# novanet.net
KiCad netlist of a schematic drawn in EAGLE
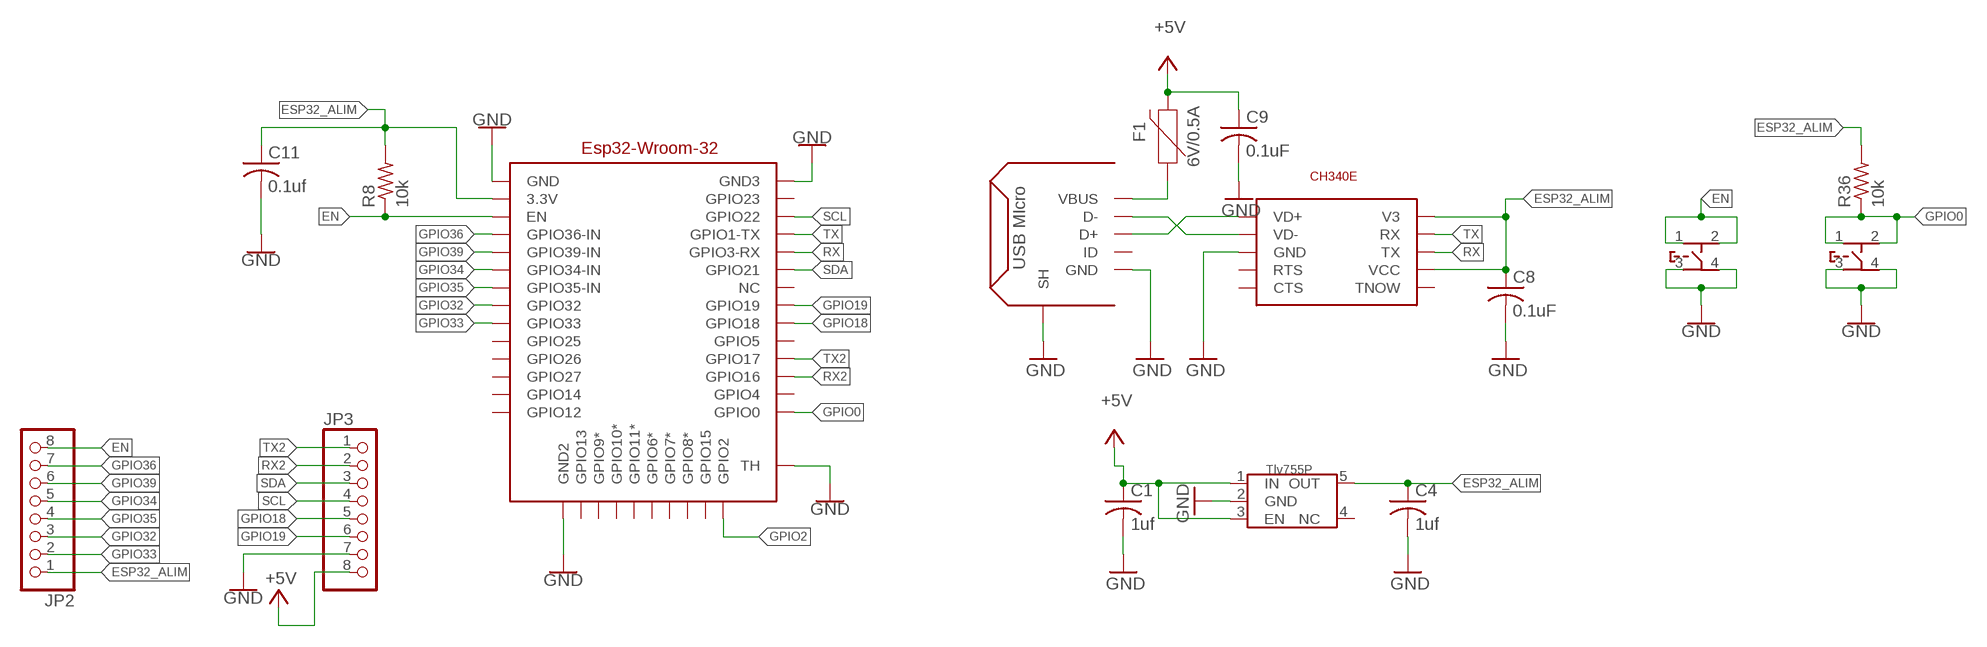
[diagram p0: schematic, sheet 1]

(export (version "E")
  (design (tool "Eeschema 10.0.6"))
  (components
    (comp (ref "C1")
      (value "1uf")
      (footprint "eagle-import:C0603")
      (libsource (lib "eagle-import") (part "C-USC0603"))
    )
    (comp (ref "C4")
      (value "1uf")
      (footprint "eagle-import:C0603")
      (libsource (lib "eagle-import") (part "C-USC0603"))
    )
    (comp (ref "C8")
      (value "0.1uF")
      (footprint "eagle-import:C0603")
      (libsource (lib "eagle-import") (part "C-USC0603"))
    )
    (comp (ref "C9")
      (value "0.1uF")
      (footprint "eagle-import:C0603")
      (libsource (lib "eagle-import") (part "C-USC0603"))
    )
    (comp (ref "C11")
      (value "0.1uf")
      (footprint "eagle-import:C0603")
      (libsource (lib "eagle-import") (part "C-USC0603"))
    )
    (comp (ref "F1")
      (value "6V/0.5A")
      (footprint "eagle-import:1206")
      (libsource (lib "eagle-import") (part "PPTC_HALF-AMP"))
    )
    (comp (ref "JP2")
      (value "PINHD-1X8")
      (footprint "eagle-import:1X08")
      (libsource (lib "eagle-import") (part "PINHD-1X8"))
    )
    (comp (ref "JP3")
      (value "PINHD-1X8")
      (footprint "eagle-import:1X08")
      (libsource (lib "eagle-import") (part "PINHD-1X8"))
    )
    (comp (ref "R8")
      (value "10k")
      (footprint "eagle-import:R0603")
      (libsource (lib "eagle-import") (part "R-US_R0603"))
    )
    (comp (ref "R36")
      (value "10k")
      (footprint "eagle-import:R0603")
      (libsource (lib "eagle-import") (part "R-US_R0603"))
    )
    (comp (ref "U$1")
      (value "TLV755P-3.3SOT-23-5")
      (footprint "eagle-import:DBV_R-PDSO-G5")
      (libsource (lib "eagle-import") (part "TLV755P-3.3SOT-23-5"))
    )
    (comp (ref "U$3")
      (value "CH340E")
      (footprint "eagle-import:MSOP-10")
      (libsource (lib "eagle-import") (part "CH340E"))
    )
    (comp (ref "U$4")
      (value "ESP32-WROM-32")
      (footprint "eagle-import:ESP-32FOOTPRINT")
      (libsource (lib "eagle-import") (part "ESP32-WROM-32"))
    )
    (comp (ref "U$14")
      (value "USB-MICROTIPOC")
      (footprint "eagle-import:USB-MICRO")
      (libsource (lib "eagle-import") (part "USB-MICROTIPOC"))
    )
    (comp (ref "U$22")
      (value "XUNPU")
      (footprint "eagle-import:TS-1089S")
      (libsource (lib "eagle-import") (part "XUNPU"))
    )
    (comp (ref "U$23")
      (value "XUNPU")
      (footprint "eagle-import:TS-1089S")
      (libsource (lib "eagle-import") (part "XUNPU"))
    )
  )
  (nets
    (net (code "1") (name "+5V") (class "Default")
      (node (ref "C1") (pin "1") (pinfunction "1_1") (pintype "passive"))
      (node (ref "C9") (pin "1") (pinfunction "1_1") (pintype "passive"))
      (node (ref "F1") (pin "2") (pinfunction "2_2") (pintype "bidirectional"))
      (node (ref "JP3") (pin "8") (pinfunction "8_8") (pintype "passive"))
      (node (ref "U$1") (pin "1") (pinfunction "IN_1") (pintype "bidirectional"))
      (node (ref "U$1") (pin "3") (pinfunction "EN_3") (pintype "bidirectional"))
    )
    (net (code "2") (name "EN") (class "Default")
      (node (ref "JP2") (pin "8") (pinfunction "8_8") (pintype "passive"))
      (node (ref "R8") (pin "1") (pinfunction "1_1") (pintype "passive"))
      (node (ref "U$22") (pin "1") (pinfunction "1_1") (pintype "bidirectional"))
      (node (ref "U$22") (pin "2") (pinfunction "2_2") (pintype "bidirectional"))
      (node (ref "U$4") (pin "EN") (pinfunction "EN_EN") (pintype "bidirectional"))
    )
    (net (code "3") (name "ESP32_ALIM") (class "Default")
      (node (ref "C11") (pin "1") (pinfunction "1_1") (pintype "passive"))
      (node (ref "C4") (pin "1") (pinfunction "1_1") (pintype "passive"))
      (node (ref "C8") (pin "1") (pinfunction "1_1") (pintype "passive"))
      (node (ref "JP2") (pin "1") (pinfunction "1_1") (pintype "passive"))
      (node (ref "R36") (pin "2") (pinfunction "2_2") (pintype "passive"))
      (node (ref "R8") (pin "2") (pinfunction "2_2") (pintype "passive"))
      (node (ref "U$1") (pin "5") (pinfunction "OUT_5") (pintype "bidirectional"))
      (node (ref "U$3") (pin "V3") (pinfunction "V3_V3") (pintype "bidirectional"))
      (node (ref "U$3") (pin "VCC") (pinfunction "VCC_VCC") (pintype "bidirectional"))
      (node (ref "U$4") (pin "3.3V") (pinfunction "3.3V_3.3V") (pintype "bidirectional"))
    )
    (net (code "4") (name "GND") (class "Default")
      (node (ref "C1") (pin "2") (pinfunction "2_2") (pintype "passive"))
      (node (ref "C11") (pin "2") (pinfunction "2_2") (pintype "passive"))
      (node (ref "C4") (pin "2") (pinfunction "2_2") (pintype "passive"))
      (node (ref "C8") (pin "2") (pinfunction "2_2") (pintype "passive"))
      (node (ref "C9") (pin "2") (pinfunction "2_2") (pintype "passive"))
      (node (ref "JP3") (pin "7") (pinfunction "7_7") (pintype "passive"))
      (node (ref "U$1") (pin "2") (pinfunction "GND_2") (pintype "bidirectional"))
      (node (ref "U$14") (pin "GND") (pinfunction "GND_GND") (pintype "bidirectional"))
      (node (ref "U$14") (pin "P$1") (pinfunction "SH_P$1") (pintype "bidirectional"))
      (node (ref "U$14") (pin "P$2") (pinfunction "SH_P$2") (pintype "bidirectional"))
      (node (ref "U$14") (pin "P$3") (pinfunction "SH_P$3") (pintype "bidirectional"))
      (node (ref "U$14") (pin "P$4") (pinfunction "SH_P$4") (pintype "bidirectional"))
      (node (ref "U$22") (pin "3") (pinfunction "3_3") (pintype "bidirectional"))
      (node (ref "U$22") (pin "4") (pinfunction "4_4") (pintype "bidirectional"))
      (node (ref "U$23") (pin "3") (pinfunction "3_3") (pintype "bidirectional"))
      (node (ref "U$23") (pin "4") (pinfunction "4_4") (pintype "bidirectional"))
      (node (ref "U$3") (pin "GND") (pinfunction "GND_GND") (pintype "bidirectional"))
      (node (ref "U$4") (pin "GND") (pinfunction "GND_GND") (pintype "bidirectional"))
      (node (ref "U$4") (pin "GND2") (pinfunction "GND2_GND2") (pintype "bidirectional"))
      (node (ref "U$4") (pin "GND3") (pinfunction "GND3_GND3") (pintype "bidirectional"))
      (node (ref "U$4") (pin "TH") (pinfunction "TH_TH") (pintype "bidirectional"))
    )
    (net (code "5") (name "GPIO0") (class "Default")
      (node (ref "R36") (pin "1") (pinfunction "1_1") (pintype "passive"))
      (node (ref "U$23") (pin "1") (pinfunction "1_1") (pintype "bidirectional"))
      (node (ref "U$23") (pin "2") (pinfunction "2_2") (pintype "bidirectional"))
      (node (ref "U$4") (pin "GPIO0") (pinfunction "GPIO0_GPIO0") (pintype "bidirectional"))
    )
    (net (code "6") (name "GPIO2") (class "Default")
      (node (ref "U$4") (pin "GPIO2") (pinfunction "GPIO2_GPIO2") (pintype "bidirectional"))
    )
    (net (code "7") (name "GPIO18") (class "Default")
      (node (ref "JP3") (pin "5") (pinfunction "5_5") (pintype "passive"))
      (node (ref "U$4") (pin "GPIO18") (pinfunction "GPIO18_GPIO18") (pintype "bidirectional"))
    )
    (net (code "8") (name "GPIO19") (class "Default")
      (node (ref "JP3") (pin "6") (pinfunction "6_6") (pintype "passive"))
      (node (ref "U$4") (pin "GPIO19") (pinfunction "GPIO19_GPIO19") (pintype "bidirectional"))
    )
    (net (code "9") (name "GPIO32") (class "Default")
      (node (ref "JP2") (pin "3") (pinfunction "3_3") (pintype "passive"))
      (node (ref "U$4") (pin "GPIO32") (pinfunction "GPIO32_GPIO32") (pintype "bidirectional"))
    )
    (net (code "10") (name "GPIO33") (class "Default")
      (node (ref "JP2") (pin "2") (pinfunction "2_2") (pintype "passive"))
      (node (ref "U$4") (pin "GPIO33") (pinfunction "GPIO33_GPIO33") (pintype "bidirectional"))
    )
    (net (code "11") (name "GPIO34") (class "Default")
      (node (ref "JP2") (pin "5") (pinfunction "5_5") (pintype "passive"))
      (node (ref "U$4") (pin "GPIO34") (pinfunction "GPIO34-IN_GPIO34") (pintype "bidirectional"))
    )
    (net (code "12") (name "GPIO35") (class "Default")
      (node (ref "JP2") (pin "4") (pinfunction "4_4") (pintype "passive"))
      (node (ref "U$4") (pin "GPIO35") (pinfunction "GPIO35-IN_GPIO35") (pintype "bidirectional"))
    )
    (net (code "13") (name "GPIO36") (class "Default")
      (node (ref "JP2") (pin "7") (pinfunction "7_7") (pintype "passive"))
      (node (ref "U$4") (pin "GPIO36") (pinfunction "GPIO36-IN_GPIO36") (pintype "bidirectional"))
    )
    (net (code "14") (name "GPIO39") (class "Default")
      (node (ref "JP2") (pin "6") (pinfunction "6_6") (pintype "passive"))
      (node (ref "U$4") (pin "GPIO39") (pinfunction "GPIO39-IN_GPIO39") (pintype "bidirectional"))
    )
    (net (code "15") (name "Net-(F1-Pad1)") (class "Default")
      (node (ref "F1") (pin "1") (pinfunction "1_1") (pintype "bidirectional"))
      (node (ref "U$14") (pin "VBUS") (pinfunction "VBUS_VBUS") (pintype "bidirectional"))
    )
    (net (code "16") (name "Net-(U$14-PadD+)") (class "Default")
      (node (ref "U$14") (pin "D+") (pinfunction "D+_D+") (pintype "bidirectional"))
      (node (ref "U$3") (pin "VD+") (pinfunction "VD+_VD+") (pintype "bidirectional"))
    )
    (net (code "17") (name "Net-(U$14-PadD-)") (class "Default")
      (node (ref "U$14") (pin "D-") (pinfunction "D-_D-") (pintype "bidirectional"))
      (node (ref "U$3") (pin "VD-") (pinfunction "VD-_VD-") (pintype "bidirectional"))
    )
    (net (code "18") (name "RX") (class "Default")
      (node (ref "U$3") (pin "TX") (pinfunction "TX_TX") (pintype "bidirectional"))
      (node (ref "U$4") (pin "GPIO3") (pinfunction "GPIO3-RX_GPIO3") (pintype "bidirectional"))
    )
    (net (code "19") (name "RX2") (class "Default")
      (node (ref "JP3") (pin "2") (pinfunction "2_2") (pintype "passive"))
      (node (ref "U$4") (pin "GPIO16") (pinfunction "GPIO16_GPIO16") (pintype "bidirectional"))
    )
    (net (code "20") (name "SCL") (class "Default")
      (node (ref "JP3") (pin "4") (pinfunction "4_4") (pintype "passive"))
      (node (ref "U$4") (pin "GPO22") (pinfunction "GPIO22_GPO22") (pintype "bidirectional"))
    )
    (net (code "21") (name "SDA") (class "Default")
      (node (ref "JP3") (pin "3") (pinfunction "3_3") (pintype "passive"))
      (node (ref "U$4") (pin "GPIO21") (pinfunction "GPIO21_GPIO21") (pintype "bidirectional"))
    )
    (net (code "22") (name "TX") (class "Default")
      (node (ref "U$3") (pin "RX") (pinfunction "RX_RX") (pintype "bidirectional"))
      (node (ref "U$4") (pin "GPIO1") (pinfunction "GPIO1-TX_GPIO1") (pintype "bidirectional"))
    )
    (net (code "23") (name "TX2") (class "Default")
      (node (ref "JP3") (pin "1") (pinfunction "1_1") (pintype "passive"))
      (node (ref "U$4") (pin "GPIO17") (pinfunction "GPIO17_GPIO17") (pintype "bidirectional"))
    )
    (net (code "24") (name "unconnected-(U$1-NC-Pad4)") (class "Default")
      (node (ref "U$1") (pin "4") (pinfunction "NC_4") (pintype "bidirectional"))
    )
    (net (code "25") (name "unconnected-(U$3-PadCTS)") (class "Default")
      (node (ref "U$3") (pin "CTS") (pinfunction "CTS_CTS") (pintype "bidirectional"))
    )
    (net (code "26") (name "unconnected-(U$3-PadRTS)") (class "Default")
      (node (ref "U$3") (pin "RTS") (pinfunction "RTS_RTS") (pintype "bidirectional"))
    )
    (net (code "27") (name "unconnected-(U$3-PadTNOW)") (class "Default")
      (node (ref "U$3") (pin "TNOW") (pinfunction "TNOW_TNOW") (pintype "bidirectional"))
    )
    (net (code "28") (name "unconnected-(U$4-GPIO6*-PadGPIO6)") (class "Default")
      (node (ref "U$4") (pin "GPIO6") (pinfunction "GPIO6*_GPIO6") (pintype "bidirectional"))
    )
    (net (code "29") (name "unconnected-(U$4-GPIO7*-PadGPIO7)") (class "Default")
      (node (ref "U$4") (pin "GPIO7") (pinfunction "GPIO7*_GPIO7") (pintype "bidirectional"))
    )
    (net (code "30") (name "unconnected-(U$4-GPIO8*-PadGPIO8)") (class "Default")
      (node (ref "U$4") (pin "GPIO8") (pinfunction "GPIO8*_GPIO8") (pintype "bidirectional"))
    )
    (net (code "31") (name "unconnected-(U$4-GPIO9*-PadGPIO9)") (class "Default")
      (node (ref "U$4") (pin "GPIO9") (pinfunction "GPIO9*_GPIO9") (pintype "bidirectional"))
    )
    (net (code "32") (name "unconnected-(U$4-GPIO10*-PadGPIO10)") (class "Default")
      (node (ref "U$4") (pin "GPIO10") (pinfunction "GPIO10*_GPIO10") (pintype "bidirectional"))
    )
    (net (code "33") (name "unconnected-(U$4-GPIO11*-PadGPIO11)") (class "Default")
      (node (ref "U$4") (pin "GPIO11") (pinfunction "GPIO11*_GPIO11") (pintype "bidirectional"))
    )
    (net (code "34") (name "unconnected-(U$4-PadGPIO4)") (class "Default")
      (node (ref "U$4") (pin "GPIO4") (pinfunction "GPIO4_GPIO4") (pintype "bidirectional"))
    )
    (net (code "35") (name "unconnected-(U$4-PadGPIO5)") (class "Default")
      (node (ref "U$4") (pin "GPIO5") (pinfunction "GPIO5_GPIO5") (pintype "bidirectional"))
    )
    (net (code "36") (name "unconnected-(U$4-PadGPIO12)") (class "Default")
      (node (ref "U$4") (pin "GPIO12") (pinfunction "GPIO12_GPIO12") (pintype "bidirectional"))
    )
    (net (code "37") (name "unconnected-(U$4-PadGPIO13)") (class "Default")
      (node (ref "U$4") (pin "GPIO13") (pinfunction "GPIO13_GPIO13") (pintype "bidirectional"))
    )
    (net (code "38") (name "unconnected-(U$4-PadGPIO14)") (class "Default")
      (node (ref "U$4") (pin "GPIO14") (pinfunction "GPIO14_GPIO14") (pintype "bidirectional"))
    )
    (net (code "39") (name "unconnected-(U$4-PadGPIO15)") (class "Default")
      (node (ref "U$4") (pin "GPIO15") (pinfunction "GPIO15_GPIO15") (pintype "bidirectional"))
    )
    (net (code "40") (name "unconnected-(U$4-PadGPIO23)") (class "Default")
      (node (ref "U$4") (pin "GPIO23") (pinfunction "GPIO23_GPIO23") (pintype "bidirectional"))
    )
    (net (code "41") (name "unconnected-(U$4-PadGPIO25)") (class "Default")
      (node (ref "U$4") (pin "GPIO25") (pinfunction "GPIO25_GPIO25") (pintype "bidirectional"))
    )
    (net (code "42") (name "unconnected-(U$4-PadGPIO26)") (class "Default")
      (node (ref "U$4") (pin "GPIO26") (pinfunction "GPIO26_GPIO26") (pintype "bidirectional"))
    )
    (net (code "43") (name "unconnected-(U$4-PadGPIO27)") (class "Default")
      (node (ref "U$4") (pin "GPIO27") (pinfunction "GPIO27_GPIO27") (pintype "bidirectional"))
    )
    (net (code "44") (name "unconnected-(U$4-PadNC)") (class "Default")
      (node (ref "U$4") (pin "NC") (pinfunction "NC_NC") (pintype "bidirectional"))
    )
    (net (code "45") (name "unconnected-(U$14-PadID)") (class "Default")
      (node (ref "U$14") (pin "ID") (pinfunction "ID_ID") (pintype "bidirectional"))
    )
  )
)
